# schematic.net
KiCad netlist of a schematic drawn in EAGLE
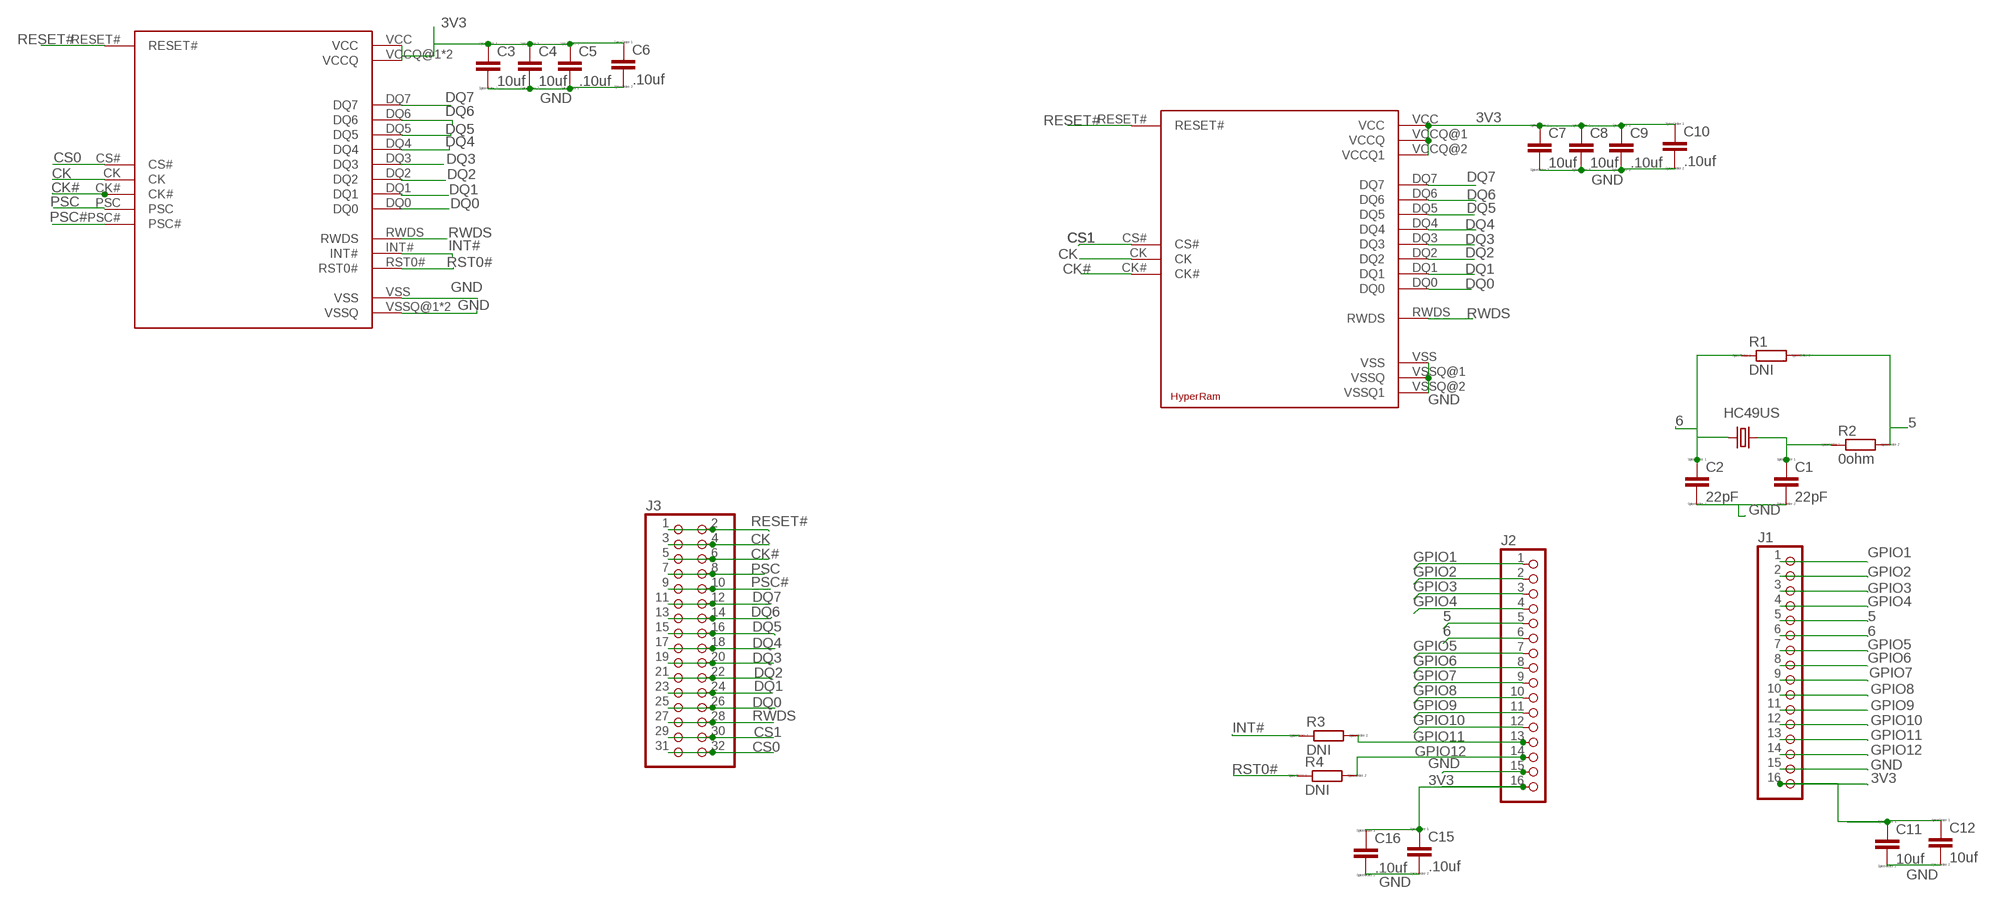
[diagram p0: schematic, sheet 1]

(export (version "E")
  (design (tool "Eeschema 10.0.6"))
  (components
    (comp (ref "C1")
      (value "22pF")
      (footprint "eagle-import:C0603")
      (libsource (lib "eagle-import") (part "eagle-ltspice_217_CC0603"))
    )
    (comp (ref "C2")
      (value "22pF")
      (footprint "eagle-import:C0603")
      (libsource (lib "eagle-import") (part "eagle-ltspice_217_CC0603"))
    )
    (comp (ref "C3")
      (value "10uf")
      (footprint "eagle-import:C0402")
      (libsource (lib "eagle-import") (part "CC0402"))
    )
    (comp (ref "C4")
      (value "10uf")
      (footprint "eagle-import:C0402")
      (libsource (lib "eagle-import") (part "CC0402"))
    )
    (comp (ref "C5")
      (value ".10uf")
      (footprint "eagle-import:C0402")
      (libsource (lib "eagle-import") (part "CC0402"))
    )
    (comp (ref "C6")
      (value ".10uf")
      (footprint "eagle-import:C0402")
      (libsource (lib "eagle-import") (part "CC0402"))
    )
    (comp (ref "C7")
      (value "10uf")
      (footprint "eagle-import:C0402")
      (libsource (lib "eagle-import") (part "CC0402"))
    )
    (comp (ref "C8")
      (value "10uf")
      (footprint "eagle-import:C0402")
      (libsource (lib "eagle-import") (part "CC0402"))
    )
    (comp (ref "C9")
      (value ".10uf")
      (footprint "eagle-import:C0402")
      (libsource (lib "eagle-import") (part "CC0402"))
    )
    (comp (ref "C10")
      (value ".10uf")
      (footprint "eagle-import:C0402")
      (libsource (lib "eagle-import") (part "CC0402"))
    )
    (comp (ref "C11")
      (value "10uf")
      (footprint "eagle-import:C0402")
      (libsource (lib "eagle-import") (part "CC0402"))
    )
    (comp (ref "C12")
      (value "10uf")
      (footprint "eagle-import:C0402")
      (libsource (lib "eagle-import") (part "CC0402"))
    )
    (comp (ref "C15")
      (value ".10uf")
      (footprint "eagle-import:C0402")
      (libsource (lib "eagle-import") (part "CC0402"))
    )
    (comp (ref "C16")
      (value ".10uf")
      (footprint "eagle-import:C0402")
      (libsource (lib "eagle-import") (part "CC0402"))
    )
    (comp (ref "HC49US")
      (value "12 Mhz")
      (footprint "eagle-import:HC49UP")
      (libsource (lib "eagle-import") (part "MODIFIEDSMD"))
    )
    (comp (ref "J1")
      (value "PINHD-1X16")
      (footprint "eagle-import:1X16")
      (libsource (lib "eagle-import") (part "PINHD-1X16"))
    )
    (comp (ref "J2")
      (value "PINHD-1X16")
      (footprint "eagle-import:1X16")
      (libsource (lib "eagle-import") (part "PINHD-1X16"))
    )
    (comp (ref "J3")
      (value "PINHD-2X16")
      (footprint "eagle-import:2X16")
      (libsource (lib "eagle-import") (part "PINHD-2X16"))
    )
    (comp (ref "R1")
      (value "DNI")
      (footprint "eagle-import:R0603")
      (libsource (lib "eagle-import") (part "RR0603"))
    )
    (comp (ref "R2")
      (value "0ohm")
      (footprint "eagle-import:R0603")
      (libsource (lib "eagle-import") (part "RR0603"))
    )
    (comp (ref "R3")
      (value "DNI")
      (footprint "eagle-import:R0603")
      (libsource (lib "eagle-import") (part "RR0603"))
    )
    (comp (ref "R4")
      (value "DNI")
      (footprint "eagle-import:R0603")
      (libsource (lib "eagle-import") (part "RR0603"))
    )
    (comp (ref "U$1")
      (value "HYPERFLASH_MEMORY")
      (footprint "eagle-import:BGA-24")
      (libsource (lib "eagle-import") (part "hyperflash_HYPERFLASH_MEMORY"))
    )
    (comp (ref "U$2")
      (value "HYPERFLASH_MEMORY")
      (footprint "eagle-import:BGA-24_RAM")
      (libsource (lib "eagle-import") (part "HYPERFLASH_MEMORY"))
    )
  )
  (nets
    (net (code "1") (name "/3V3") (class "Default")
      (node (ref "C10") (pin "1") (pinfunction "1_1") (pintype "passive"))
      (node (ref "C11") (pin "1") (pinfunction "1_1") (pintype "passive"))
      (node (ref "C12") (pin "1") (pinfunction "1_1") (pintype "passive"))
      (node (ref "C15") (pin "1") (pinfunction "1_1") (pintype "passive"))
      (node (ref "C16") (pin "1") (pinfunction "1_1") (pintype "passive"))
      (node (ref "C3") (pin "1") (pinfunction "1_1") (pintype "passive"))
      (node (ref "C4") (pin "1") (pinfunction "1_1") (pintype "passive"))
      (node (ref "C5") (pin "1") (pinfunction "1_1") (pintype "passive"))
      (node (ref "C6") (pin "1") (pinfunction "1_1") (pintype "passive"))
      (node (ref "C7") (pin "1") (pinfunction "1_1") (pintype "passive"))
      (node (ref "C8") (pin "1") (pinfunction "1_1") (pintype "passive"))
      (node (ref "C9") (pin "1") (pinfunction "1_1") (pintype "passive"))
      (node (ref "J1") (pin "16") (pinfunction "16_16") (pintype "passive"))
      (node (ref "J2") (pin "16") (pinfunction "16_16") (pintype "passive"))
      (node (ref "U$1") (pin "VCC") (pinfunction "VCC_VCC") (pintype "bidirectional"))
      (node (ref "U$1") (pin "VCCQ@1") (pinfunction "VCCQ_VCCQ@1") (pintype "bidirectional"))
      (node (ref "U$1") (pin "VCCQ@2") (pinfunction "VCCQ_VCCQ@2") (pintype "bidirectional"))
      (node (ref "U$2") (pin "VCC") (pinfunction "VCC_VCC") (pintype "bidirectional"))
      (node (ref "U$2") (pin "VCCQ@1") (pinfunction "VCCQ_VCCQ@1") (pintype "bidirectional"))
      (node (ref "U$2") (pin "VCCQ@2") (pinfunction "VCCQ1_VCCQ@2") (pintype "bidirectional"))
    )
    (net (code "2") (name "/5") (class "Default")
      (node (ref "J1") (pin "5") (pinfunction "5_5") (pintype "passive"))
      (node (ref "J2") (pin "5") (pinfunction "5_5") (pintype "passive"))
      (node (ref "R1") (pin "2") (pinfunction "2_2") (pintype "passive"))
      (node (ref "R2") (pin "2") (pinfunction "2_2") (pintype "passive"))
    )
    (net (code "3") (name "/6") (class "Default")
      (node (ref "C2") (pin "1") (pinfunction "1_1") (pintype "passive"))
      (node (ref "HC49US") (pin "1") (pinfunction "1_1") (pintype "passive"))
      (node (ref "HC49US") (pin "P$1") (pinfunction "1_P$1") (pintype "passive"))
      (node (ref "J1") (pin "6") (pinfunction "6_6") (pintype "passive"))
      (node (ref "J2") (pin "6") (pinfunction "6_6") (pintype "passive"))
      (node (ref "R1") (pin "1") (pinfunction "1_1") (pintype "passive"))
    )
    (net (code "4") (name "/CK") (class "Default")
      (node (ref "J3") (pin "3") (pinfunction "3_3") (pintype "passive"))
      (node (ref "J3") (pin "4") (pinfunction "4_4") (pintype "passive"))
      (node (ref "U$1") (pin "CK") (pinfunction "CK_CK") (pintype "bidirectional"))
      (node (ref "U$2") (pin "CK") (pinfunction "CK_CK") (pintype "bidirectional"))
    )
    (net (code "5") (name "/CK#") (class "Default")
      (node (ref "J3") (pin "5") (pinfunction "5_5") (pintype "passive"))
      (node (ref "J3") (pin "6") (pinfunction "6_6") (pintype "passive"))
      (node (ref "U$1") (pin "CK#") (pinfunction "CK#_CK#") (pintype "bidirectional"))
      (node (ref "U$2") (pin "CK#") (pinfunction "CK#_CK#") (pintype "bidirectional"))
    )
    (net (code "6") (name "/CS0") (class "Default")
      (node (ref "J3") (pin "31") (pinfunction "31_31") (pintype "passive"))
      (node (ref "J3") (pin "32") (pinfunction "32_32") (pintype "passive"))
      (node (ref "U$1") (pin "CS#") (pinfunction "CS#_CS#") (pintype "bidirectional"))
    )
    (net (code "7") (name "/CS1") (class "Default")
      (node (ref "J3") (pin "29") (pinfunction "29_29") (pintype "passive"))
      (node (ref "J3") (pin "30") (pinfunction "30_30") (pintype "passive"))
      (node (ref "U$2") (pin "CS#") (pinfunction "CS#_CS#") (pintype "bidirectional"))
    )
    (net (code "8") (name "/DQ0") (class "Default")
      (node (ref "J3") (pin "25") (pinfunction "25_25") (pintype "passive"))
      (node (ref "J3") (pin "26") (pinfunction "26_26") (pintype "passive"))
      (node (ref "U$1") (pin "DQ0") (pinfunction "DQ0_DQ0") (pintype "bidirectional"))
      (node (ref "U$2") (pin "DQ0") (pinfunction "DQ0_DQ0") (pintype "bidirectional"))
    )
    (net (code "9") (name "/DQ1") (class "Default")
      (node (ref "J3") (pin "23") (pinfunction "23_23") (pintype "passive"))
      (node (ref "J3") (pin "24") (pinfunction "24_24") (pintype "passive"))
      (node (ref "U$1") (pin "DQ1") (pinfunction "DQ1_DQ1") (pintype "bidirectional"))
      (node (ref "U$2") (pin "DQ1") (pinfunction "DQ1_DQ1") (pintype "bidirectional"))
    )
    (net (code "10") (name "/DQ2") (class "Default")
      (node (ref "J3") (pin "21") (pinfunction "21_21") (pintype "passive"))
      (node (ref "J3") (pin "22") (pinfunction "22_22") (pintype "passive"))
      (node (ref "U$1") (pin "DQ2") (pinfunction "DQ2_DQ2") (pintype "bidirectional"))
      (node (ref "U$2") (pin "DQ2") (pinfunction "DQ2_DQ2") (pintype "bidirectional"))
    )
    (net (code "11") (name "/DQ3") (class "Default")
      (node (ref "J3") (pin "19") (pinfunction "19_19") (pintype "passive"))
      (node (ref "J3") (pin "20") (pinfunction "20_20") (pintype "passive"))
      (node (ref "U$1") (pin "DQ3") (pinfunction "DQ3_DQ3") (pintype "bidirectional"))
      (node (ref "U$2") (pin "DQ3") (pinfunction "DQ3_DQ3") (pintype "bidirectional"))
    )
    (net (code "12") (name "/DQ4") (class "Default")
      (node (ref "J3") (pin "17") (pinfunction "17_17") (pintype "passive"))
      (node (ref "J3") (pin "18") (pinfunction "18_18") (pintype "passive"))
      (node (ref "U$1") (pin "DQ4") (pinfunction "DQ4_DQ4") (pintype "bidirectional"))
      (node (ref "U$2") (pin "DQ4") (pinfunction "DQ4_DQ4") (pintype "bidirectional"))
    )
    (net (code "13") (name "/DQ5") (class "Default")
      (node (ref "J3") (pin "15") (pinfunction "15_15") (pintype "passive"))
      (node (ref "J3") (pin "16") (pinfunction "16_16") (pintype "passive"))
      (node (ref "U$1") (pin "DQ5") (pinfunction "DQ5_DQ5") (pintype "bidirectional"))
      (node (ref "U$2") (pin "DQ5") (pinfunction "DQ5_DQ5") (pintype "bidirectional"))
    )
    (net (code "14") (name "/DQ6") (class "Default")
      (node (ref "J3") (pin "13") (pinfunction "13_13") (pintype "passive"))
      (node (ref "J3") (pin "14") (pinfunction "14_14") (pintype "passive"))
      (node (ref "U$1") (pin "DQ6") (pinfunction "DQ6_DQ6") (pintype "bidirectional"))
      (node (ref "U$2") (pin "DQ6") (pinfunction "DQ6_DQ6") (pintype "bidirectional"))
    )
    (net (code "15") (name "/DQ7") (class "Default")
      (node (ref "J3") (pin "11") (pinfunction "11_11") (pintype "passive"))
      (node (ref "J3") (pin "12") (pinfunction "12_12") (pintype "passive"))
      (node (ref "U$1") (pin "DQ7") (pinfunction "DQ7_DQ7") (pintype "bidirectional"))
      (node (ref "U$2") (pin "DQ7") (pinfunction "DQ7_DQ7") (pintype "bidirectional"))
    )
    (net (code "16") (name "/GND") (class "Default")
      (node (ref "C1") (pin "2") (pinfunction "2_2") (pintype "passive"))
      (node (ref "C10") (pin "2") (pinfunction "2_2") (pintype "passive"))
      (node (ref "C11") (pin "2") (pinfunction "2_2") (pintype "passive"))
      (node (ref "C12") (pin "2") (pinfunction "2_2") (pintype "passive"))
      (node (ref "C15") (pin "2") (pinfunction "2_2") (pintype "passive"))
      (node (ref "C16") (pin "2") (pinfunction "2_2") (pintype "passive"))
      (node (ref "C2") (pin "2") (pinfunction "2_2") (pintype "passive"))
      (node (ref "C3") (pin "2") (pinfunction "2_2") (pintype "passive"))
      (node (ref "C4") (pin "2") (pinfunction "2_2") (pintype "passive"))
      (node (ref "C5") (pin "2") (pinfunction "2_2") (pintype "passive"))
      (node (ref "C6") (pin "2") (pinfunction "2_2") (pintype "passive"))
      (node (ref "C7") (pin "2") (pinfunction "2_2") (pintype "passive"))
      (node (ref "C8") (pin "2") (pinfunction "2_2") (pintype "passive"))
      (node (ref "C9") (pin "2") (pinfunction "2_2") (pintype "passive"))
      (node (ref "J1") (pin "15") (pinfunction "15_15") (pintype "passive"))
      (node (ref "J2") (pin "15") (pinfunction "15_15") (pintype "passive"))
      (node (ref "U$1") (pin "VSS") (pinfunction "VSS_VSS") (pintype "bidirectional"))
      (node (ref "U$1") (pin "VSSQ@1") (pinfunction "VSSQ_VSSQ@1") (pintype "bidirectional"))
      (node (ref "U$1") (pin "VSSQ@2") (pinfunction "VSSQ_VSSQ@2") (pintype "bidirectional"))
      (node (ref "U$2") (pin "VSS") (pinfunction "VSS_VSS") (pintype "bidirectional"))
      (node (ref "U$2") (pin "VSSQ@1") (pinfunction "VSSQ_VSSQ@1") (pintype "bidirectional"))
      (node (ref "U$2") (pin "VSSQ@2") (pinfunction "VSSQ1_VSSQ@2") (pintype "bidirectional"))
    )
    (net (code "17") (name "/GPIO1") (class "Default")
      (node (ref "J1") (pin "1") (pinfunction "1_1") (pintype "passive"))
      (node (ref "J2") (pin "1") (pinfunction "1_1") (pintype "passive"))
    )
    (net (code "18") (name "/GPIO2") (class "Default")
      (node (ref "J1") (pin "2") (pinfunction "2_2") (pintype "passive"))
      (node (ref "J2") (pin "2") (pinfunction "2_2") (pintype "passive"))
    )
    (net (code "19") (name "/GPIO3") (class "Default")
      (node (ref "J1") (pin "3") (pinfunction "3_3") (pintype "passive"))
      (node (ref "J2") (pin "3") (pinfunction "3_3") (pintype "passive"))
    )
    (net (code "20") (name "/GPIO4") (class "Default")
      (node (ref "J1") (pin "4") (pinfunction "4_4") (pintype "passive"))
      (node (ref "J2") (pin "4") (pinfunction "4_4") (pintype "passive"))
    )
    (net (code "21") (name "/GPIO5") (class "Default")
      (node (ref "J1") (pin "7") (pinfunction "7_7") (pintype "passive"))
      (node (ref "J2") (pin "7") (pinfunction "7_7") (pintype "passive"))
    )
    (net (code "22") (name "/GPIO6") (class "Default")
      (node (ref "J1") (pin "8") (pinfunction "8_8") (pintype "passive"))
      (node (ref "J2") (pin "8") (pinfunction "8_8") (pintype "passive"))
    )
    (net (code "23") (name "/GPIO7") (class "Default")
      (node (ref "J1") (pin "9") (pinfunction "9_9") (pintype "passive"))
      (node (ref "J2") (pin "9") (pinfunction "9_9") (pintype "passive"))
    )
    (net (code "24") (name "/GPIO8") (class "Default")
      (node (ref "J1") (pin "10") (pinfunction "10_10") (pintype "passive"))
      (node (ref "J2") (pin "10") (pinfunction "10_10") (pintype "passive"))
    )
    (net (code "25") (name "/GPIO9") (class "Default")
      (node (ref "J1") (pin "11") (pinfunction "11_11") (pintype "passive"))
      (node (ref "J2") (pin "11") (pinfunction "11_11") (pintype "passive"))
    )
    (net (code "26") (name "/GPIO10") (class "Default")
      (node (ref "J1") (pin "12") (pinfunction "12_12") (pintype "passive"))
      (node (ref "J2") (pin "12") (pinfunction "12_12") (pintype "passive"))
    )
    (net (code "27") (name "/GPIO11") (class "Default")
      (node (ref "J1") (pin "13") (pinfunction "13_13") (pintype "passive"))
      (node (ref "J2") (pin "13") (pinfunction "13_13") (pintype "passive"))
      (node (ref "R3") (pin "2") (pinfunction "2_2") (pintype "passive"))
    )
    (net (code "28") (name "/GPIO12") (class "Default")
      (node (ref "J1") (pin "14") (pinfunction "14_14") (pintype "passive"))
      (node (ref "J2") (pin "14") (pinfunction "14_14") (pintype "passive"))
      (node (ref "R4") (pin "2") (pinfunction "2_2") (pintype "passive"))
    )
    (net (code "29") (name "/INT#") (class "Default")
      (node (ref "R3") (pin "1") (pinfunction "1_1") (pintype "passive"))
      (node (ref "U$1") (pin "INT#") (pinfunction "INT#_INT#") (pintype "bidirectional"))
    )
    (net (code "30") (name "/PSC") (class "Default")
      (node (ref "J3") (pin "7") (pinfunction "7_7") (pintype "passive"))
      (node (ref "J3") (pin "8") (pinfunction "8_8") (pintype "passive"))
      (node (ref "U$1") (pin "PSC") (pinfunction "PSC_PSC") (pintype "bidirectional"))
    )
    (net (code "31") (name "/PSC#") (class "Default")
      (node (ref "J3") (pin "10") (pinfunction "10_10") (pintype "passive"))
      (node (ref "J3") (pin "9") (pinfunction "9_9") (pintype "passive"))
      (node (ref "U$1") (pin "PSC#") (pinfunction "PSC#_PSC#") (pintype "bidirectional"))
    )
    (net (code "32") (name "/RESET#") (class "Default")
      (node (ref "J3") (pin "1") (pinfunction "1_1") (pintype "passive"))
      (node (ref "J3") (pin "2") (pinfunction "2_2") (pintype "passive"))
      (node (ref "U$1") (pin "RESET#") (pinfunction "RESET#_RESET#") (pintype "bidirectional"))
      (node (ref "U$2") (pin "RESET#") (pinfunction "RESET#_RESET#") (pintype "bidirectional"))
    )
    (net (code "33") (name "/RST0#") (class "Default")
      (node (ref "R4") (pin "1") (pinfunction "1_1") (pintype "passive"))
      (node (ref "U$1") (pin "RST0#") (pinfunction "RST0#_RST0#") (pintype "bidirectional"))
    )
    (net (code "34") (name "/RWDS") (class "Default")
      (node (ref "J3") (pin "27") (pinfunction "27_27") (pintype "passive"))
      (node (ref "J3") (pin "28") (pinfunction "28_28") (pintype "passive"))
      (node (ref "U$1") (pin "RWDS") (pinfunction "RWDS_RWDS") (pintype "bidirectional"))
      (node (ref "U$2") (pin "RWDS") (pinfunction "RWDS_RWDS") (pintype "bidirectional"))
    )
    (net (code "35") (name "Net-(C1-Pad1)") (class "Default")
      (node (ref "C1") (pin "1") (pinfunction "1_1") (pintype "passive"))
      (node (ref "HC49US") (pin "2") (pinfunction "2_2") (pintype "passive"))
      (node (ref "HC49US") (pin "P$2") (pinfunction "2_P$2") (pintype "passive"))
      (node (ref "R2") (pin "1") (pinfunction "1_1") (pintype "passive"))
    )
  )
)
